# 12V_supply.net
KiCad netlist of a schematic drawn in EAGLE
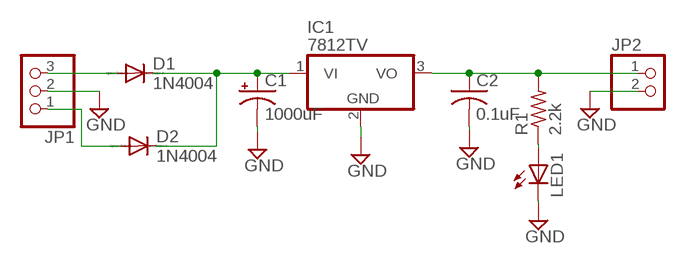
[diagram p0: schematic, sheet 1]

(export (version "E")
  (design (tool "Eeschema 10.0.6"))
  (components
    (comp (ref "C1")
      (value "1000uF")
      (footprint "eagle-import:E5-10,5")
      (libsource (lib "eagle-import") (part "CPOL-USE5-10.5"))
    )
    (comp (ref "C2")
      (value "0.1uF")
      (footprint "eagle-import:C025-025X050")
      (libsource (lib "eagle-import") (part "C-US025-025X050"))
    )
    (comp (ref "D1")
      (value "1N4004")
      (footprint "eagle-import:DO41-10")
      (libsource (lib "eagle-import") (part "1N4004"))
    )
    (comp (ref "D2")
      (value "1N4004")
      (footprint "eagle-import:DO41-10")
      (libsource (lib "eagle-import") (part "1N4004"))
    )
    (comp (ref "IC1")
      (value "7812TV")
      (footprint "eagle-import:TO220V")
      (libsource (lib "eagle-import") (part "78TV12"))
    )
    (comp (ref "JP1")
      (value "PINHD-1X3")
      (footprint "eagle-import:1X03")
      (libsource (lib "eagle-import") (part "PINHD-1X3"))
    )
    (comp (ref "JP2")
      (value "PINHD-1X2")
      (footprint "eagle-import:1X02")
      (libsource (lib "eagle-import") (part "PINHD-1X2"))
    )
    (comp (ref "LED1")
      (value "LED5MM")
      (footprint "eagle-import:LED5MM")
      (libsource (lib "eagle-import") (part "LED5MM"))
    )
    (comp (ref "R1")
      (value "2.2k")
      (footprint "eagle-import:0207_10")
      (libsource (lib "eagle-import") (part "R-US_0207/10"))
    )
  )
  (nets
    (net (code "1") (name "GND") (class "Default")
      (node (ref "C1") (pin "-") (pinfunction "-_-") (pintype "passive"))
      (node (ref "C2") (pin "2") (pinfunction "2_2") (pintype "passive"))
      (node (ref "IC1") (pin "2") (pinfunction "GND_2") (pintype "passive"))
      (node (ref "JP1") (pin "2") (pinfunction "2_2") (pintype "passive"))
      (node (ref "JP2") (pin "2") (pinfunction "2_2") (pintype "passive"))
      (node (ref "LED1") (pin "K") (pinfunction "C_K") (pintype "passive"))
    )
    (net (code "2") (name "Net-(D1-PadA)") (class "Default")
      (node (ref "D1") (pin "A") (pinfunction "A_A") (pintype "passive"))
      (node (ref "JP1") (pin "3") (pinfunction "3_3") (pintype "passive"))
    )
    (net (code "3") (name "Net-(D2-PadA)") (class "Default")
      (node (ref "D2") (pin "A") (pinfunction "A_A") (pintype "passive"))
      (node (ref "JP1") (pin "1") (pinfunction "1_1") (pintype "passive"))
    )
    (net (code "4") (name "Net-(IC1-VI)") (class "Default")
      (node (ref "C1") (pin "+") (pinfunction "+_+") (pintype "passive"))
      (node (ref "D1") (pin "C") (pinfunction "C_C") (pintype "passive"))
      (node (ref "D2") (pin "C") (pinfunction "C_C") (pintype "passive"))
      (node (ref "IC1") (pin "1") (pinfunction "VI_1") (pintype "input"))
    )
    (net (code "5") (name "Net-(IC1-VO)") (class "Default")
      (node (ref "C2") (pin "1") (pinfunction "1_1") (pintype "passive"))
      (node (ref "IC1") (pin "3") (pinfunction "VO_3") (pintype "passive"))
      (node (ref "JP2") (pin "1") (pinfunction "1_1") (pintype "passive"))
      (node (ref "R1") (pin "2") (pinfunction "2_2") (pintype "passive"))
    )
    (net (code "6") (name "Net-(LED1-PadA)") (class "Default")
      (node (ref "LED1") (pin "A") (pinfunction "A_A") (pintype "passive"))
      (node (ref "R1") (pin "1") (pinfunction "1_1") (pintype "passive"))
    )
  )
)
